# Grove_Base_HAT_For_Raspberry_Pi_Zero.net
KiCad netlist of a schematic drawn in EAGLE
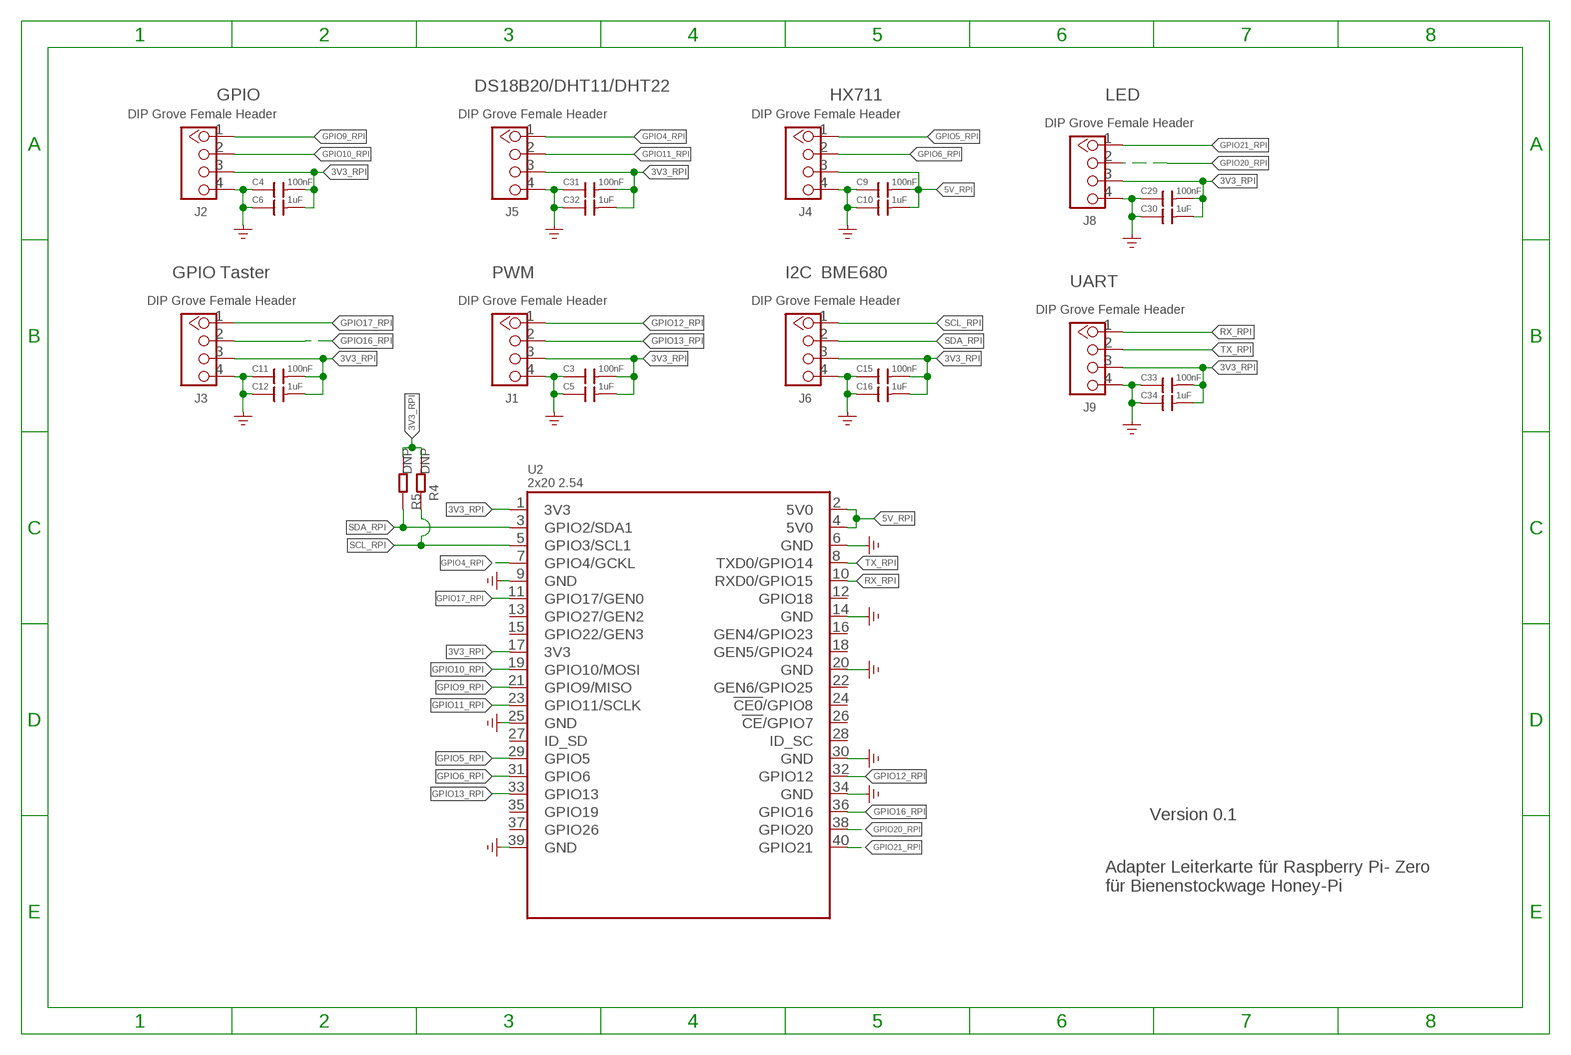
[diagram p0: schematic, sheet 1]

(export (version "E")
  (design (tool "Eeschema 10.0.6"))
  (components
    (comp (ref "C3")
      (value "100nF")
      (footprint "eagle-import:C0603")
      (libsource (lib "eagle-import") (part "C-0603"))
    )
    (comp (ref "C4")
      (value "100nF")
      (footprint "eagle-import:C0603")
      (libsource (lib "eagle-import") (part "C-0603"))
    )
    (comp (ref "C5")
      (value "1uF")
      (footprint "eagle-import:C0603")
      (libsource (lib "eagle-import") (part "C-0603"))
    )
    (comp (ref "C6")
      (value "1uF")
      (footprint "eagle-import:C0603")
      (libsource (lib "eagle-import") (part "C-0603"))
    )
    (comp (ref "C9")
      (value "100nF")
      (footprint "eagle-import:C0603")
      (libsource (lib "eagle-import") (part "C-0603"))
    )
    (comp (ref "C10")
      (value "1uF")
      (footprint "eagle-import:C0603")
      (libsource (lib "eagle-import") (part "C-0603"))
    )
    (comp (ref "C11")
      (value "100nF")
      (footprint "eagle-import:C0603")
      (libsource (lib "eagle-import") (part "C-0603"))
    )
    (comp (ref "C12")
      (value "1uF")
      (footprint "eagle-import:C0603")
      (libsource (lib "eagle-import") (part "C-0603"))
    )
    (comp (ref "C15")
      (value "100nF")
      (footprint "eagle-import:C0603")
      (libsource (lib "eagle-import") (part "C-0603"))
    )
    (comp (ref "C16")
      (value "1uF")
      (footprint "eagle-import:C0603")
      (libsource (lib "eagle-import") (part "C-0603"))
    )
    (comp (ref "C29")
      (value "100nF")
      (footprint "eagle-import:C0603")
      (libsource (lib "eagle-import") (part "C-0603"))
    )
    (comp (ref "C30")
      (value "1uF")
      (footprint "eagle-import:C0603")
      (libsource (lib "eagle-import") (part "C-0603"))
    )
    (comp (ref "C31")
      (value "100nF")
      (footprint "eagle-import:C0603")
      (libsource (lib "eagle-import") (part "C-0603"))
    )
    (comp (ref "C32")
      (value "1uF")
      (footprint "eagle-import:C0603")
      (libsource (lib "eagle-import") (part "C-0603"))
    )
    (comp (ref "C33")
      (value "100nF")
      (footprint "eagle-import:C0603")
      (libsource (lib "eagle-import") (part "C-0603"))
    )
    (comp (ref "C34")
      (value "1uF")
      (footprint "eagle-import:C0603")
      (libsource (lib "eagle-import") (part "C-0603"))
    )
    (comp (ref "J1")
      (value "DIP Grove Female Header")
      (footprint "eagle-import:HW4-2.0")
      (libsource (lib "eagle-import") (part "GROVE-CONNECTOR-DIP-2.0"))
    )
    (comp (ref "J2")
      (value "DIP Grove Female Header")
      (footprint "eagle-import:HW4-2.0")
      (libsource (lib "eagle-import") (part "GROVE-CONNECTOR-DIP-2.0"))
    )
    (comp (ref "J3")
      (value "DIP Grove Female Header")
      (footprint "eagle-import:HW4-2.0")
      (libsource (lib "eagle-import") (part "GROVE-CONNECTOR-DIP-2.0"))
    )
    (comp (ref "J4")
      (value "DIP Grove Female Header")
      (footprint "eagle-import:HW4-2.0")
      (libsource (lib "eagle-import") (part "GROVE-CONNECTOR-DIP-2.0"))
    )
    (comp (ref "J5")
      (value "DIP Grove Female Header")
      (footprint "eagle-import:HW4-2.0")
      (libsource (lib "eagle-import") (part "GROVE-CONNECTOR-DIP-2.0"))
    )
    (comp (ref "J6")
      (value "DIP Grove Female Header")
      (footprint "eagle-import:HW4-2.0")
      (libsource (lib "eagle-import") (part "GROVE-CONNECTOR-DIP-2.0"))
    )
    (comp (ref "J8")
      (value "DIP Grove Female Header")
      (footprint "eagle-import:HW4-2.0")
      (libsource (lib "eagle-import") (part "GROVE-CONNECTOR-DIP-2.0"))
    )
    (comp (ref "J9")
      (value "DIP Grove Female Header")
      (footprint "eagle-import:HW4-2.0")
      (libsource (lib "eagle-import") (part "GROVE-CONNECTOR-DIP-2.0"))
    )
    (comp (ref "R4")
      (value "DNP")
      (footprint "eagle-import:R0603")
      (libsource (lib "eagle-import") (part "R-0603"))
    )
    (comp (ref "R5")
      (value "DNP")
      (footprint "eagle-import:R0603")
      (libsource (lib "eagle-import") (part "R-0603"))
    )
    (comp (ref "U2")
      (value "2x20 2.54")
      (footprint "eagle-import:RASPBERRYPI_BASTELSTUBE_V13_RASPI_BOARD_B+_FULL")
      (libsource (lib "eagle-import") (part "RPI-ZERO-65X30"))
    )
  )
  (nets
    (net (code "1") (name "3V3_RPI") (class "Default")
      (node (ref "C11") (pin "2") (pinfunction "2_2") (pintype "passive"))
      (node (ref "C12") (pin "2") (pinfunction "2_2") (pintype "passive"))
      (node (ref "C15") (pin "2") (pinfunction "2_2") (pintype "passive"))
      (node (ref "C16") (pin "2") (pinfunction "2_2") (pintype "passive"))
      (node (ref "C29") (pin "2") (pinfunction "2_2") (pintype "passive"))
      (node (ref "C3") (pin "2") (pinfunction "2_2") (pintype "passive"))
      (node (ref "C30") (pin "2") (pinfunction "2_2") (pintype "passive"))
      (node (ref "C31") (pin "2") (pinfunction "2_2") (pintype "passive"))
      (node (ref "C32") (pin "2") (pinfunction "2_2") (pintype "passive"))
      (node (ref "C33") (pin "2") (pinfunction "2_2") (pintype "passive"))
      (node (ref "C34") (pin "2") (pinfunction "2_2") (pintype "passive"))
      (node (ref "C4") (pin "2") (pinfunction "2_2") (pintype "passive"))
      (node (ref "C5") (pin "2") (pinfunction "2_2") (pintype "passive"))
      (node (ref "C6") (pin "2") (pinfunction "2_2") (pintype "passive"))
      (node (ref "J1") (pin "3") (pinfunction "3_3") (pintype "bidirectional"))
      (node (ref "J2") (pin "3") (pinfunction "3_3") (pintype "bidirectional"))
      (node (ref "J3") (pin "3") (pinfunction "3_3") (pintype "bidirectional"))
      (node (ref "J5") (pin "3") (pinfunction "3_3") (pintype "bidirectional"))
      (node (ref "J6") (pin "3") (pinfunction "3_3") (pintype "bidirectional"))
      (node (ref "J8") (pin "3") (pinfunction "3_3") (pintype "bidirectional"))
      (node (ref "J9") (pin "3") (pinfunction "3_3") (pintype "bidirectional"))
      (node (ref "R4") (pin "2") (pinfunction "2_2") (pintype "passive"))
      (node (ref "R5") (pin "2") (pinfunction "2_2") (pintype "passive"))
      (node (ref "U2") (pin "1") (pinfunction "3V3_1") (pintype "power_in"))
      (node (ref "U2") (pin "17") (pinfunction "3V3_17") (pintype "power_in"))
    )
    (net (code "2") (name "5V_RPI") (class "Default")
      (node (ref "C10") (pin "2") (pinfunction "2_2") (pintype "passive"))
      (node (ref "C9") (pin "2") (pinfunction "2_2") (pintype "passive"))
      (node (ref "J4") (pin "3") (pinfunction "3_3") (pintype "bidirectional"))
      (node (ref "U2") (pin "2") (pinfunction "5V0_2") (pintype "power_in"))
      (node (ref "U2") (pin "4") (pinfunction "5V0_4") (pintype "power_in"))
    )
    (net (code "3") (name "GND_POWER") (class "Default")
      (node (ref "C10") (pin "1") (pinfunction "1_1") (pintype "passive"))
      (node (ref "C11") (pin "1") (pinfunction "1_1") (pintype "passive"))
      (node (ref "C12") (pin "1") (pinfunction "1_1") (pintype "passive"))
      (node (ref "C15") (pin "1") (pinfunction "1_1") (pintype "passive"))
      (node (ref "C16") (pin "1") (pinfunction "1_1") (pintype "passive"))
      (node (ref "C29") (pin "1") (pinfunction "1_1") (pintype "passive"))
      (node (ref "C3") (pin "1") (pinfunction "1_1") (pintype "passive"))
      (node (ref "C30") (pin "1") (pinfunction "1_1") (pintype "passive"))
      (node (ref "C31") (pin "1") (pinfunction "1_1") (pintype "passive"))
      (node (ref "C32") (pin "1") (pinfunction "1_1") (pintype "passive"))
      (node (ref "C33") (pin "1") (pinfunction "1_1") (pintype "passive"))
      (node (ref "C34") (pin "1") (pinfunction "1_1") (pintype "passive"))
      (node (ref "C4") (pin "1") (pinfunction "1_1") (pintype "passive"))
      (node (ref "C5") (pin "1") (pinfunction "1_1") (pintype "passive"))
      (node (ref "C6") (pin "1") (pinfunction "1_1") (pintype "passive"))
      (node (ref "C9") (pin "1") (pinfunction "1_1") (pintype "passive"))
      (node (ref "J1") (pin "4") (pinfunction "4_4") (pintype "bidirectional"))
      (node (ref "J2") (pin "4") (pinfunction "4_4") (pintype "bidirectional"))
      (node (ref "J3") (pin "4") (pinfunction "4_4") (pintype "bidirectional"))
      (node (ref "J4") (pin "4") (pinfunction "4_4") (pintype "bidirectional"))
      (node (ref "J5") (pin "4") (pinfunction "4_4") (pintype "bidirectional"))
      (node (ref "J6") (pin "4") (pinfunction "4_4") (pintype "bidirectional"))
      (node (ref "J8") (pin "4") (pinfunction "4_4") (pintype "bidirectional"))
      (node (ref "J9") (pin "4") (pinfunction "4_4") (pintype "bidirectional"))
      (node (ref "U2") (pin "14") (pinfunction "GND_14") (pintype "power_in"))
      (node (ref "U2") (pin "20") (pinfunction "GND_20") (pintype "power_in"))
      (node (ref "U2") (pin "25") (pinfunction "GND_25") (pintype "power_in"))
      (node (ref "U2") (pin "30") (pinfunction "GND_30") (pintype "power_in"))
      (node (ref "U2") (pin "34") (pinfunction "GND_34") (pintype "power_in"))
      (node (ref "U2") (pin "39") (pinfunction "GND_39") (pintype "power_in"))
      (node (ref "U2") (pin "6") (pinfunction "GND_6") (pintype "power_in"))
      (node (ref "U2") (pin "9") (pinfunction "GND_9") (pintype "power_in"))
    )
    (net (code "4") (name "GPIO4_RPI") (class "Default")
      (node (ref "J5") (pin "1") (pinfunction "1_1") (pintype "bidirectional"))
      (node (ref "U2") (pin "7") (pinfunction "GPIO4/GCKL_7") (pintype "bidirectional"))
    )
    (net (code "5") (name "GPIO5_RPI") (class "Default")
      (node (ref "J4") (pin "1") (pinfunction "1_1") (pintype "bidirectional"))
      (node (ref "U2") (pin "29") (pinfunction "GPIO5_29") (pintype "bidirectional"))
    )
    (net (code "6") (name "GPIO6_RPI") (class "Default")
      (node (ref "J4") (pin "2") (pinfunction "2_2") (pintype "bidirectional"))
      (node (ref "U2") (pin "31") (pinfunction "GPIO6_31") (pintype "bidirectional"))
    )
    (net (code "7") (name "GPIO9_RPI") (class "Default")
      (node (ref "J2") (pin "1") (pinfunction "1_1") (pintype "bidirectional"))
      (node (ref "U2") (pin "21") (pinfunction "GPIO9/MISO_21") (pintype "bidirectional"))
    )
    (net (code "8") (name "GPIO10_RPI") (class "Default")
      (node (ref "J2") (pin "2") (pinfunction "2_2") (pintype "bidirectional"))
      (node (ref "U2") (pin "19") (pinfunction "GPIO10/MOSI_19") (pintype "bidirectional"))
    )
    (net (code "9") (name "GPIO11_RPI") (class "Default")
      (node (ref "J5") (pin "2") (pinfunction "2_2") (pintype "bidirectional"))
      (node (ref "U2") (pin "23") (pinfunction "GPIO11/SCLK_23") (pintype "bidirectional"))
    )
    (net (code "10") (name "GPIO12_RPI") (class "Default")
      (node (ref "J1") (pin "1") (pinfunction "1_1") (pintype "bidirectional"))
      (node (ref "U2") (pin "32") (pinfunction "GPIO12_32") (pintype "bidirectional"))
    )
    (net (code "11") (name "GPIO13_RPI") (class "Default")
      (node (ref "J1") (pin "2") (pinfunction "2_2") (pintype "bidirectional"))
      (node (ref "U2") (pin "33") (pinfunction "GPIO13_33") (pintype "bidirectional"))
    )
    (net (code "12") (name "GPIO16_RPI") (class "Default")
      (node (ref "J3") (pin "2") (pinfunction "2_2") (pintype "bidirectional"))
      (node (ref "U2") (pin "36") (pinfunction "GPIO16_36") (pintype "bidirectional"))
    )
    (net (code "13") (name "GPIO17_RPI") (class "Default")
      (node (ref "J3") (pin "1") (pinfunction "1_1") (pintype "bidirectional"))
      (node (ref "U2") (pin "11") (pinfunction "GPIO17/GEN0_11") (pintype "bidirectional"))
    )
    (net (code "14") (name "GPIO20_RPI") (class "Default")
      (node (ref "J8") (pin "2") (pinfunction "2_2") (pintype "bidirectional"))
      (node (ref "U2") (pin "38") (pinfunction "GPIO20_38") (pintype "bidirectional"))
    )
    (net (code "15") (name "GPIO21_RPI") (class "Default")
      (node (ref "J8") (pin "1") (pinfunction "1_1") (pintype "bidirectional"))
      (node (ref "U2") (pin "40") (pinfunction "GPIO21_40") (pintype "bidirectional"))
    )
    (net (code "16") (name "RX_RPI") (class "Default")
      (node (ref "J9") (pin "1") (pinfunction "1_1") (pintype "bidirectional"))
      (node (ref "U2") (pin "10") (pinfunction "RXD0/GPIO15_10") (pintype "bidirectional"))
    )
    (net (code "17") (name "SCL_RPI") (class "Default")
      (node (ref "J6") (pin "1") (pinfunction "1_1") (pintype "bidirectional"))
      (node (ref "R4") (pin "1") (pinfunction "1_1") (pintype "passive"))
      (node (ref "U2") (pin "5") (pinfunction "GPIO3/SCL1_5") (pintype "bidirectional"))
    )
    (net (code "18") (name "SDA_RPI") (class "Default")
      (node (ref "J6") (pin "2") (pinfunction "2_2") (pintype "bidirectional"))
      (node (ref "R5") (pin "1") (pinfunction "1_1") (pintype "passive"))
      (node (ref "U2") (pin "3") (pinfunction "GPIO2/SDA1_3") (pintype "bidirectional"))
    )
    (net (code "19") (name "TX_RPI") (class "Default")
      (node (ref "J9") (pin "2") (pinfunction "2_2") (pintype "bidirectional"))
      (node (ref "U2") (pin "8") (pinfunction "TXD0/GPIO14_8") (pintype "bidirectional"))
    )
    (net (code "20") (name "unconnected-(U2-GEN4{slash}GPIO23-Pad16)") (class "Default")
      (node (ref "U2") (pin "16") (pinfunction "GEN4/GPIO23_16") (pintype "bidirectional"))
    )
    (net (code "21") (name "unconnected-(U2-GEN5{slash}GPIO24-Pad18)") (class "Default")
      (node (ref "U2") (pin "18") (pinfunction "GEN5/GPIO24_18") (pintype "bidirectional"))
    )
    (net (code "22") (name "unconnected-(U2-GEN6{slash}GPIO25-Pad22)") (class "Default")
      (node (ref "U2") (pin "22") (pinfunction "GEN6/GPIO25_22") (pintype "bidirectional"))
    )
    (net (code "23") (name "unconnected-(U2-GPIO18-Pad12)") (class "Default")
      (node (ref "U2") (pin "12") (pinfunction "GPIO18_12") (pintype "bidirectional"))
    )
    (net (code "24") (name "unconnected-(U2-GPIO19-Pad35)") (class "Default")
      (node (ref "U2") (pin "35") (pinfunction "GPIO19_35") (pintype "bidirectional"))
    )
    (net (code "25") (name "unconnected-(U2-GPIO22{slash}GEN3-Pad15)") (class "Default")
      (node (ref "U2") (pin "15") (pinfunction "GPIO22/GEN3_15") (pintype "bidirectional"))
    )
    (net (code "26") (name "unconnected-(U2-GPIO26-Pad37)") (class "Default")
      (node (ref "U2") (pin "37") (pinfunction "GPIO26_37") (pintype "bidirectional"))
    )
    (net (code "27") (name "unconnected-(U2-GPIO27{slash}GEN2-Pad13)") (class "Default")
      (node (ref "U2") (pin "13") (pinfunction "GPIO27/GEN2_13") (pintype "bidirectional"))
    )
    (net (code "28") (name "unconnected-(U2-ID_SC-Pad28)") (class "Default")
      (node (ref "U2") (pin "28") (pinfunction "ID_SC_28") (pintype "bidirectional"))
    )
    (net (code "29") (name "unconnected-(U2-ID_SD-Pad27)") (class "Default")
      (node (ref "U2") (pin "27") (pinfunction "ID_SD_27") (pintype "bidirectional"))
    )
    (net (code "30") (name "unconnected-(U2-~{CE0}{slash}GPIO8-Pad24)") (class "Default")
      (node (ref "U2") (pin "24") (pinfunction "~{CE0}/GPIO8_24") (pintype "bidirectional"))
    )
    (net (code "31") (name "unconnected-(U2-~{CE}{slash}GPIO7-Pad26)") (class "Default")
      (node (ref "U2") (pin "26") (pinfunction "~{CE}/GPIO7_26") (pintype "bidirectional"))
    )
  )
)
